# Qwiic_UV_Sensor_-_ZOPT220x.net
KiCad netlist of a schematic drawn in EAGLE
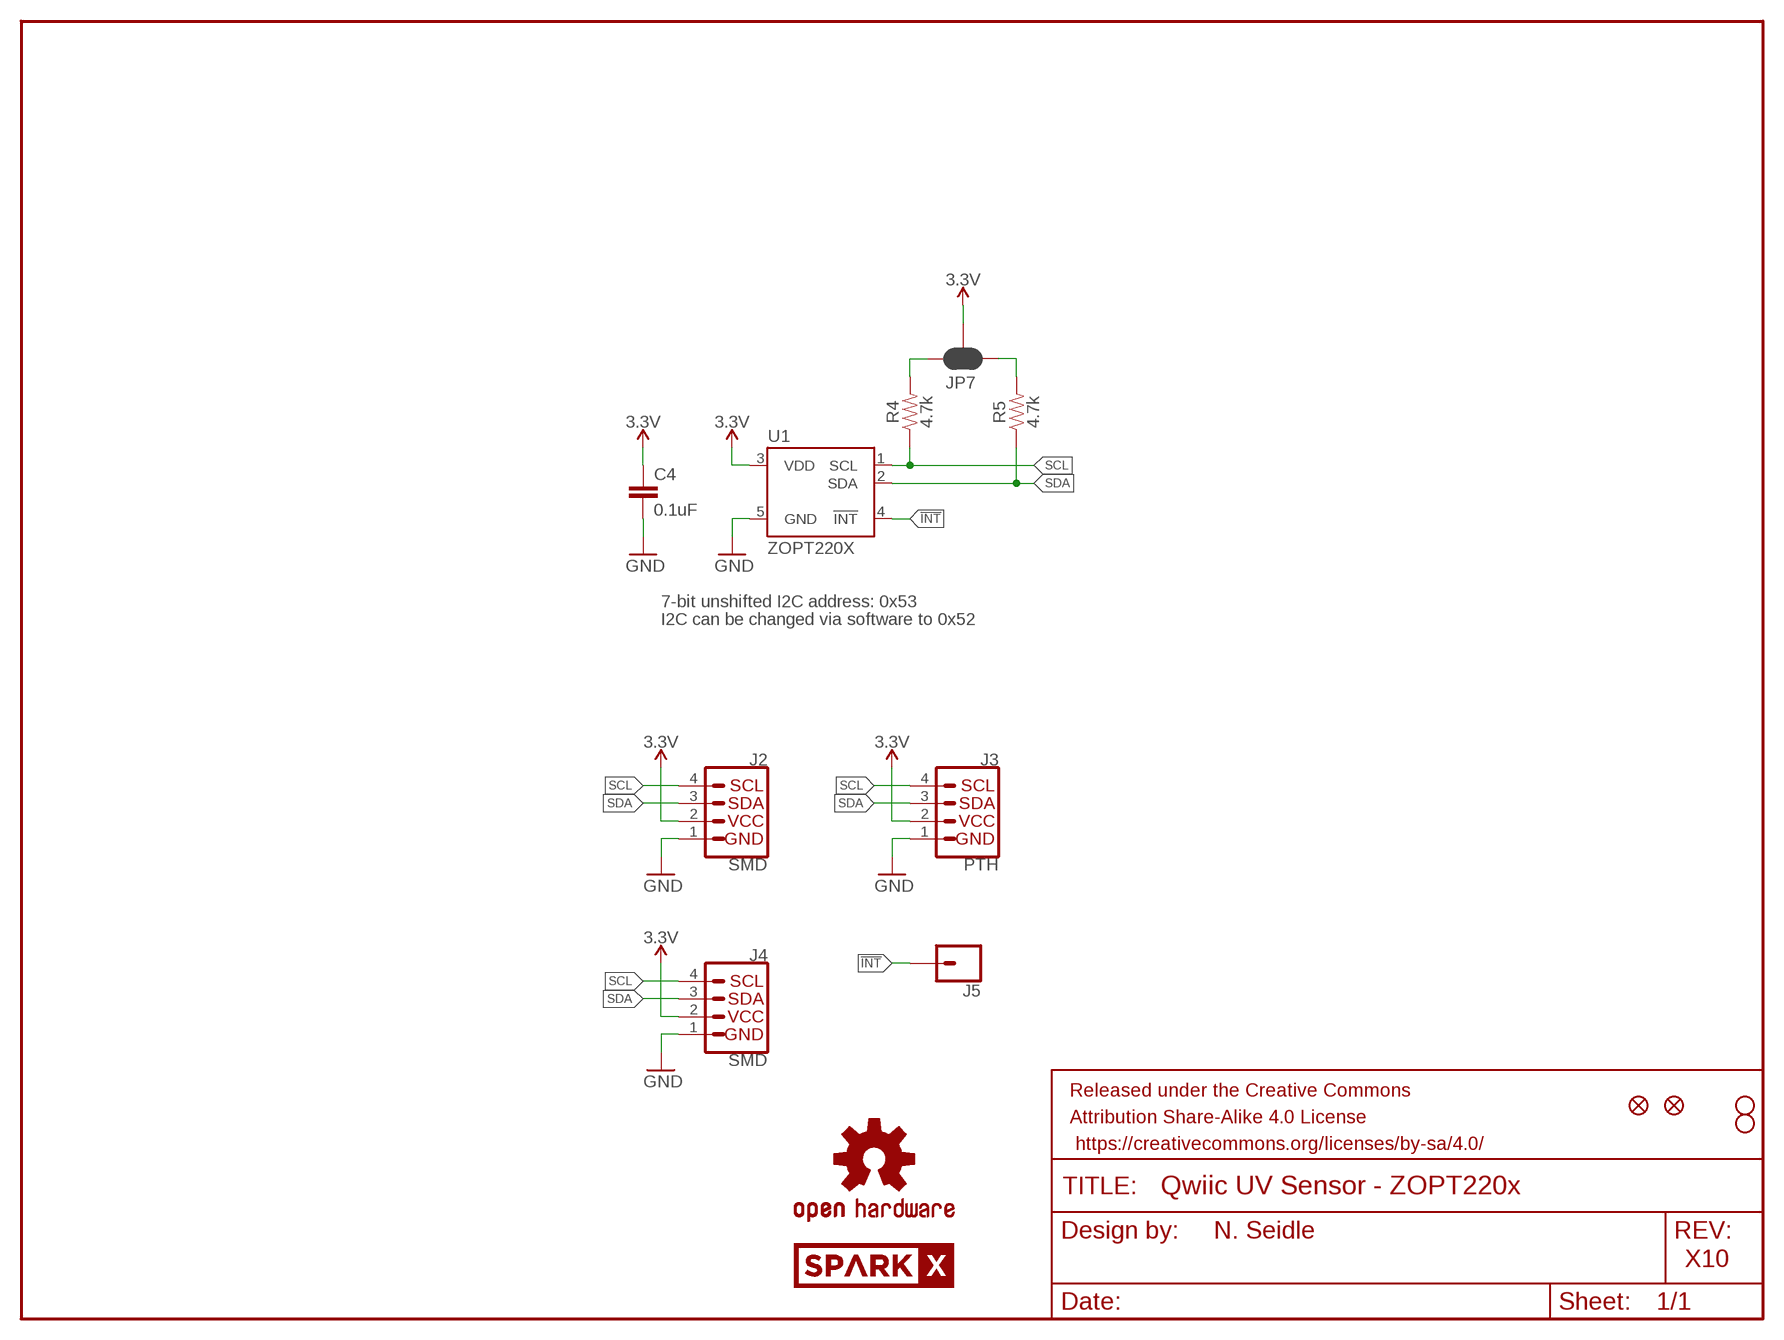
[diagram p0: schematic, sheet 1]

(export (version "E")
  (design (tool "Eeschema 10.0.6"))
  (components
    (comp (ref "C4")
      (value "0.1uF")
      (footprint "eagle-import:0603")
      (libsource (lib "eagle-import") (part "0.1UF-0603-25V-(+80/-20%)"))
    )
    (comp (ref "FRAME1")
      (value "FRAME-LETTER")
      (footprint "eagle-import:CREATIVE_COMMONS")
      (libsource (lib "eagle-import") (part "FRAME-LETTER"))
    )
    (comp (ref "J2")
      (value "SMD")
      (footprint "eagle-import:1X04_1MM_RA")
      (libsource (lib "eagle-import") (part "I2C_STANDARDJS-1MM"))
    )
    (comp (ref "J3")
      (value "PTH")
      (footprint "eagle-import:1X04_NO_SILK")
      (libsource (lib "eagle-import") (part "I2C_STANDARD_NO_SILK"))
    )
    (comp (ref "J4")
      (value "SMD")
      (footprint "eagle-import:1X04_1MM_RA")
      (libsource (lib "eagle-import") (part "I2C_STANDARDJS-1MM"))
    )
    (comp (ref "J5")
      (value "CONN_01PTH_NO_SILK_YES_STOP")
      (footprint "eagle-import:1X01_NO_SILK")
      (libsource (lib "eagle-import") (part "CONN_01PTH_NO_SILK_YES_STOP"))
    )
    (comp (ref "JP2")
      (value "FIDUCIALUFIDUCIAL")
      (footprint "eagle-import:MICRO-FIDUCIAL")
      (libsource (lib "eagle-import") (part "FIDUCIALUFIDUCIAL"))
    )
    (comp (ref "JP3")
      (value "STAND-OFF")
      (footprint "eagle-import:STAND-OFF")
      (libsource (lib "eagle-import") (part "STAND-OFF"))
    )
    (comp (ref "JP4")
      (value "STAND-OFF")
      (footprint "eagle-import:STAND-OFF")
      (libsource (lib "eagle-import") (part "STAND-OFF"))
    )
    (comp (ref "JP6")
      (value "FIDUCIALUFIDUCIAL")
      (footprint "eagle-import:MICRO-FIDUCIAL")
      (libsource (lib "eagle-import") (part "FIDUCIALUFIDUCIAL"))
    )
    (comp (ref "JP7")
      (value "JUMPER-SMT_3_2-NC_PASTE_SILK")
      (footprint "eagle-import:SMT-JUMPER_3_2-NC_PASTE_SILK")
      (libsource (lib "eagle-import") (part "JUMPER-SMT_3_2-NC_PASTE_SILK"))
    )
    (comp (ref "LOGO1")
      (value "OSHW-LOGOMINI")
      (footprint "eagle-import:OSHW-LOGO-MINI")
      (libsource (lib "eagle-import") (part "OSHW-LOGOMINI"))
    )
    (comp (ref "R4")
      (value "4.7k")
      (footprint "eagle-import:0603")
      (libsource (lib "eagle-import") (part "4.7KOHM-0603-1/10W-1%"))
    )
    (comp (ref "R5")
      (value "4.7k")
      (footprint "eagle-import:0603")
      (libsource (lib "eagle-import") (part "4.7KOHM-0603-1/10W-1%"))
    )
    (comp (ref "U$1")
      (value "SPARKX-LOGO4")
      (footprint "eagle-import:SPARKX-MEDIUM")
      (libsource (lib "eagle-import") (part "SPARKX-LOGO4"))
    )
    (comp (ref "U$2")
      (value "SPARKX-LOGO4")
      (footprint "eagle-import:SPARKX-MEDIUM")
      (libsource (lib "eagle-import") (part "SPARKX-LOGO4"))
    )
    (comp (ref "U1")
      (value "ZOPT220X")
      (footprint "eagle-import:LGA6")
      (libsource (lib "eagle-import") (part "ZOPT220X"))
    )
  )
  (nets
    (net (code "1") (name "/~{INT}") (class "Default")
      (node (ref "J5") (pin "1") (pinfunction "1_1") (pintype "passive"))
      (node (ref "U1") (pin "4") (pinfunction "~{INT}_4") (pintype "bidirectional"))
    )
    (net (code "2") (name "3.3V") (class "Default")
      (node (ref "C4") (pin "1") (pinfunction "1_1") (pintype "passive"))
      (node (ref "J2") (pin "2") (pinfunction "VCC_2") (pintype "power_in"))
      (node (ref "J3") (pin "2") (pinfunction "VCC_2") (pintype "power_in"))
      (node (ref "J4") (pin "2") (pinfunction "VCC_2") (pintype "power_in"))
      (node (ref "JP7") (pin "2") (pinfunction "2_2") (pintype "passive"))
      (node (ref "U1") (pin "3") (pinfunction "VDD_3") (pintype "bidirectional"))
    )
    (net (code "3") (name "GND") (class "Default")
      (node (ref "C4") (pin "2") (pinfunction "2_2") (pintype "passive"))
      (node (ref "J2") (pin "1") (pinfunction "GND_1") (pintype "power_in"))
      (node (ref "J3") (pin "1") (pinfunction "GND_1") (pintype "power_in"))
      (node (ref "J4") (pin "1") (pinfunction "GND_1") (pintype "power_in"))
      (node (ref "U1") (pin "5") (pinfunction "GND_5") (pintype "bidirectional"))
    )
    (net (code "4") (name "Net-(JP7-Pad1)") (class "Default")
      (node (ref "JP7") (pin "1") (pinfunction "1_1") (pintype "passive"))
      (node (ref "R5") (pin "2") (pinfunction "2_2") (pintype "passive"))
    )
    (net (code "5") (name "Net-(JP7-Pad3)") (class "Default")
      (node (ref "JP7") (pin "3") (pinfunction "3_3") (pintype "passive"))
      (node (ref "R4") (pin "2") (pinfunction "2_2") (pintype "passive"))
    )
    (net (code "6") (name "SCL") (class "Default")
      (node (ref "J2") (pin "4") (pinfunction "SCL_4") (pintype "passive"))
      (node (ref "J3") (pin "4") (pinfunction "SCL_4") (pintype "passive"))
      (node (ref "J4") (pin "4") (pinfunction "SCL_4") (pintype "passive"))
      (node (ref "R4") (pin "1") (pinfunction "1_1") (pintype "passive"))
      (node (ref "U1") (pin "1") (pinfunction "SCL_1") (pintype "bidirectional"))
    )
    (net (code "7") (name "SDA") (class "Default")
      (node (ref "J2") (pin "3") (pinfunction "SDA_3") (pintype "passive"))
      (node (ref "J3") (pin "3") (pinfunction "SDA_3") (pintype "passive"))
      (node (ref "J4") (pin "3") (pinfunction "SDA_3") (pintype "passive"))
      (node (ref "R5") (pin "1") (pinfunction "1_1") (pintype "passive"))
      (node (ref "U1") (pin "2") (pinfunction "SDA_2") (pintype "bidirectional"))
    )
  )
)
